# MIXR_Processing_-_SD_Card.net
KiCad netlist of a schematic drawn in Altium Designer
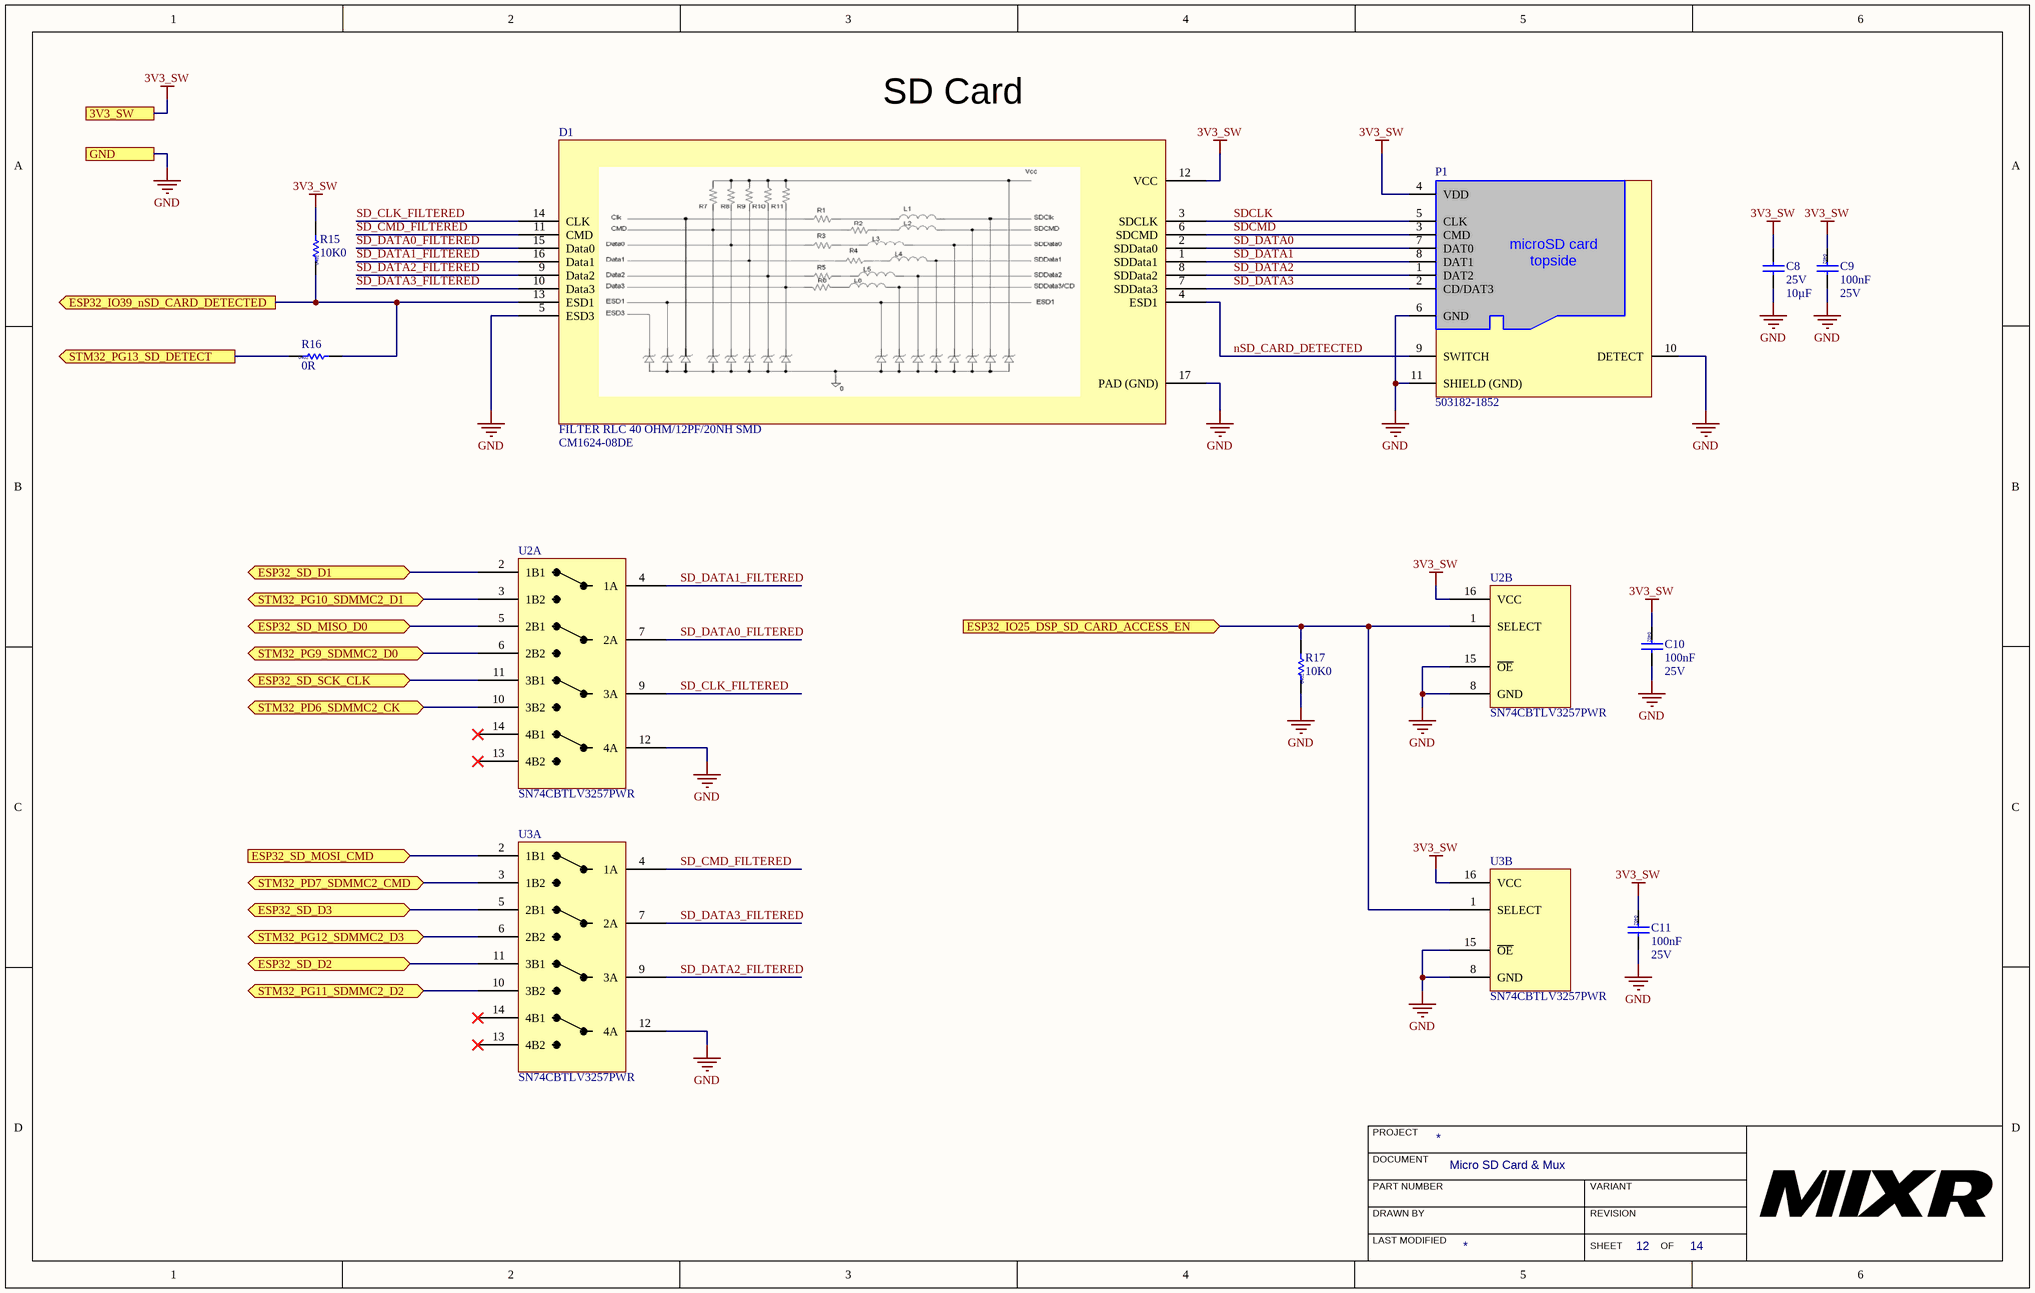
[diagram p0: MIXR Processing - SD Card.SchDoc]

(export (version "E")
  (design (tool "Eeschema 10.0.6"))
  (components
    (comp (ref "C8")
      (value "CAP CER 10uF 25V 10% X5R 0805")
      (footprint "CAP, 0805")
      (description "10µF ±10% 25V Ceramic Capacitor X5R 0805 (2012 Metric)")
      (fields
        (field (name "MANUFACTURER") "Murata Electronics North America")
        (field (name "MANUFACTURER PART NUMBER") "GRM21BR61E106KA73L")
        (field (name "VOLTAGE - RATED") "25V")
        (field (name "CAPACITANCE") "10µF")
      )
      (libsource (lib "Schematic Diagrams") (part "CAP CER 10uF 25V 10% X5R 0805"))
    )
    (comp (ref "C9")
      (value "CAP CER 0.1UF 16V X7R 0402")
      (footprint "CAP 0402")
      (description "Cap Ceramic 0.1uF 25V X7R 10% SMD 0402 125C Paper T/R")
      (fields
        (field (name "TOLERANCE") "10%")
        (field (name "CAPACITANCE") "100nF")
        (field (name "VOLTAGE") "25V")
        (field (name "MANUFACTURER") "Murata")
      )
      (libsource (lib "Schematic Diagrams") (part "CAP CER 0.1UF 16V X7R 0402"))
    )
    (comp (ref "C10")
      (value "CAP CER 0.1UF 16V X7R 0402")
      (footprint "CAP 0402")
      (description "Cap Ceramic 0.1uF 25V X7R 10% SMD 0402 125C Paper T/R")
      (fields
        (field (name "TOLERANCE") "10%")
        (field (name "CAPACITANCE") "100nF")
        (field (name "VOLTAGE") "25V")
        (field (name "MANUFACTURER") "Murata")
      )
      (libsource (lib "Schematic Diagrams") (part "CAP CER 0.1UF 16V X7R 0402"))
    )
    (comp (ref "C11")
      (value "CAP CER 0.1UF 16V X7R 0402")
      (footprint "CAP 0402")
      (description "Cap Ceramic 0.1uF 25V X7R 10% SMD 0402 125C Paper T/R")
      (fields
        (field (name "TOLERANCE") "10%")
        (field (name "CAPACITANCE") "100nF")
        (field (name "VOLTAGE") "25V")
        (field (name "MANUFACTURER") "Murata")
      )
      (libsource (lib "Schematic Diagrams") (part "CAP CER 0.1UF 16V X7R 0402"))
    )
    (comp (ref "D1")
      (value "FILTER RLC 40 OHM/12PF/20NH SMD")
      (footprint "QFN0P135X330X55_HS-17M")
      (description "RLC EMI Filter 3rd Order Low Pass 6 Channel R = 40Ohms, C = 12pF, L = 20nH 16-UFDFN Exposed Pad")
      (fields (field (name "MANUFACTURER PART NUMBER 1") "CM1624-08DE"))
      (libsource (lib "Schematic Diagrams") (part "FILTER RLC 40 OHM/12PF/20NH SMD"))
    )
    (comp (ref "P1")
      (value "CONN MICRO-SD ULTRA-LOW 8CKT")
      (footprint "CONN MICRO-SD HOLDER MOLEX 503182-1852")
      (description "9 (8 + 1) Position Card Connector microSD™ Surface Mount, Right Angle Gold")
      (fields (field (name "MANUFACTURER") "Molex") (field (name "MANUFACTURER PART NUMBER") "503182-1852"))
      (libsource (lib "Schematic Diagrams") (part "CONN MICRO-SD ULTRA-LOW 8CKT"))
    )
    (comp (ref "R15")
      (value "RES 10K OHM 1% 1/16W 0402")
      (footprint "RES 0402")
      (description "Surface Mount Thick Film Resistor, Rc Series, 10 Kohm, 62.5 Mw, - 1%, 50 V, 0402 [1005 Metric]")
      (fields
        (field (name "TOLERANCE") "1%")
        (field (name "RESISTANCE") "10K0")
        (field (name "MANUFACTURER") "Yageo")
      )
      (libsource (lib "Schematic Diagrams") (part "RES 10K OHM 1% 1/16W 0402"))
    )
    (comp (ref "R16")
      (value "RES 0.0 OHM 1% 1/16W 0402")
      (footprint "RES 0402")
      (description "RES SMD 0 OHM JUMPER 1/16W 0402")
      (fields
        (field (name "RESISTANCE") "0R")
        (field (name "MANUFACTURER") "Yageo")
        (field (name "MANUFACTURER PART NUMBER") "RC0402JR-070RL")
      )
      (libsource (lib "Schematic Diagrams") (part "RES 0.0 OHM 1% 1/16W 0402"))
    )
    (comp (ref "R17")
      (value "RES 10K OHM 1% 1/16W 0402")
      (footprint "RES 0402")
      (description "Surface Mount Thick Film Resistor, Rc Series, 10 Kohm, 62.5 Mw, - 1%, 50 V, 0402 [1005 Metric]")
      (fields
        (field (name "TOLERANCE") "1%")
        (field (name "RESISTANCE") "10K0")
        (field (name "MANUFACTURER") "Yageo")
      )
      (libsource (lib "Schematic Diagrams") (part "RES 10K OHM 1% 1/16W 0402"))
    )
    (comp (ref "U2")
      (value "IC MUX/DEMUX 4-BIT 1-OF-2 16-TSSOP")
      (footprint "TSOP65P640X120-16N")
      (description "TEXAS INSTRUMENTS         SN74CBTLV3257PWR            1 TO 2 QUAD FET MUX/DEMUX, TSSOP-16")
      (fields
        (field (name "MANUFACTURER") "Texas Instruments")
        (field (name "MANUFACTURER PART NUMBER") "SN74CBTLV3257PWR")
      )
      (libsource (lib "Schematic Diagrams") (part "IC MUX/DEMUX 4-BIT 1-OF-2 16-TSSOP"))
    )
    (comp (ref "U3")
      (value "IC MUX/DEMUX 4-BIT 1-OF-2 16-TSSOP")
      (footprint "TSOP65P640X120-16N")
      (description "TEXAS INSTRUMENTS         SN74CBTLV3257PWR            1 TO 2 QUAD FET MUX/DEMUX, TSSOP-16")
      (fields
        (field (name "MANUFACTURER") "Texas Instruments")
        (field (name "MANUFACTURER PART NUMBER") "SN74CBTLV3257PWR")
      )
      (libsource (lib "") (part "IC MUX/DEMUX 4-BIT 1-OF-2 16-TSSOP_1"))
    )
  )
  (nets
    (net (code "1") (name "/ESP32_IO25_DSP_SD_CARD_ACCESS_EN") (class "Default")
      (node (ref "R17") (pin "2") (pinfunction "2_2") (pintype "passive"))
      (node (ref "U2") (pin "1") (pinfunction "SELECT_1") (pintype "passive"))
      (node (ref "U3") (pin "1") (pinfunction "SELECT_1") (pintype "passive"))
    )
    (net (code "2") (name "/ESP32_IO39_nSD_CARD_DETECTED") (class "Default")
      (node (ref "D1") (pin "13") (pinfunction "ESD1_13") (pintype "passive"))
      (node (ref "R15") (pin "1") (pinfunction "1_1") (pintype "passive"))
      (node (ref "R16") (pin "2") (pinfunction "2_2") (pintype "passive"))
    )
    (net (code "3") (name "/ESP32_SD_D1") (class "Default")
      (node (ref "U2") (pin "2") (pinfunction "1B1_2") (pintype "passive"))
    )
    (net (code "4") (name "/ESP32_SD_D2") (class "Default")
      (node (ref "U3") (pin "11") (pinfunction "3B1_11") (pintype "passive"))
    )
    (net (code "5") (name "/ESP32_SD_D3") (class "Default")
      (node (ref "U3") (pin "5") (pinfunction "2B1_5") (pintype "passive"))
    )
    (net (code "6") (name "/ESP32_SD_MISO_D0") (class "Default")
      (node (ref "U2") (pin "5") (pinfunction "2B1_5") (pintype "passive"))
    )
    (net (code "7") (name "/ESP32_SD_MOSI_CMD") (class "Default")
      (node (ref "U3") (pin "2") (pinfunction "1B1_2") (pintype "passive"))
    )
    (net (code "8") (name "/ESP32_SD_SCK_CLK") (class "Default")
      (node (ref "U2") (pin "11") (pinfunction "3B1_11") (pintype "passive"))
    )
    (net (code "9") (name "/SDCLK") (class "Default")
      (node (ref "D1") (pin "3") (pinfunction "SDCLK_3") (pintype "passive"))
      (node (ref "P1") (pin "5") (pinfunction "CLK_5") (pintype "passive"))
    )
    (net (code "10") (name "/SDCMD") (class "Default")
      (node (ref "D1") (pin "6") (pinfunction "SDCMD_6") (pintype "passive"))
      (node (ref "P1") (pin "3") (pinfunction "CMD_3") (pintype "passive"))
    )
    (net (code "11") (name "/SD_CLK_FILTERED") (class "Default")
      (node (ref "D1") (pin "14") (pinfunction "CLK_14") (pintype "passive"))
      (node (ref "U2") (pin "9") (pinfunction "3A_9") (pintype "passive"))
    )
    (net (code "12") (name "/SD_CMD_FILTERED") (class "Default")
      (node (ref "D1") (pin "11") (pinfunction "CMD_11") (pintype "passive"))
      (node (ref "U3") (pin "4") (pinfunction "1A_4") (pintype "passive"))
    )
    (net (code "13") (name "/SD_DATA0") (class "Default")
      (node (ref "D1") (pin "2") (pinfunction "SDData0_2") (pintype "passive"))
      (node (ref "P1") (pin "7") (pinfunction "DAT0_7") (pintype "passive"))
    )
    (net (code "14") (name "/SD_DATA0_FILTERED") (class "Default")
      (node (ref "D1") (pin "15") (pinfunction "Data0_15") (pintype "passive"))
      (node (ref "U2") (pin "7") (pinfunction "2A_7") (pintype "passive"))
    )
    (net (code "15") (name "/SD_DATA1") (class "Default")
      (node (ref "D1") (pin "1") (pinfunction "SDData1_1") (pintype "passive"))
      (node (ref "P1") (pin "8") (pinfunction "DAT1_8") (pintype "passive"))
    )
    (net (code "16") (name "/SD_DATA1_FILTERED") (class "Default")
      (node (ref "D1") (pin "16") (pinfunction "Data1_16") (pintype "passive"))
      (node (ref "U2") (pin "4") (pinfunction "1A_4") (pintype "passive"))
    )
    (net (code "17") (name "/SD_DATA2") (class "Default")
      (node (ref "D1") (pin "8") (pinfunction "SDData2_8") (pintype "passive"))
      (node (ref "P1") (pin "1") (pinfunction "DAT2_1") (pintype "passive"))
    )
    (net (code "18") (name "/SD_DATA2_FILTERED") (class "Default")
      (node (ref "D1") (pin "9") (pinfunction "Data2_9") (pintype "passive"))
      (node (ref "U3") (pin "9") (pinfunction "3A_9") (pintype "passive"))
    )
    (net (code "19") (name "/SD_DATA3") (class "Default")
      (node (ref "D1") (pin "7") (pinfunction "SDData3_7") (pintype "passive"))
      (node (ref "P1") (pin "2") (pinfunction "CD/DAT3_2") (pintype "passive"))
    )
    (net (code "20") (name "/SD_DATA3_FILTERED") (class "Default")
      (node (ref "D1") (pin "10") (pinfunction "Data3_10") (pintype "passive"))
      (node (ref "U3") (pin "7") (pinfunction "2A_7") (pintype "passive"))
    )
    (net (code "21") (name "/STM32_PD6_SDMMC2_CK") (class "Default")
      (node (ref "U2") (pin "10") (pinfunction "3B2_10") (pintype "passive"))
    )
    (net (code "22") (name "/STM32_PD7_SDMMC2_CMD") (class "Default")
      (node (ref "U3") (pin "3") (pinfunction "1B2_3") (pintype "passive"))
    )
    (net (code "23") (name "/STM32_PG9_SDMMC2_D0") (class "Default")
      (node (ref "U2") (pin "6") (pinfunction "2B2_6") (pintype "passive"))
    )
    (net (code "24") (name "/STM32_PG10_SDMMC2_D1") (class "Default")
      (node (ref "U2") (pin "3") (pinfunction "1B2_3") (pintype "passive"))
    )
    (net (code "25") (name "/STM32_PG11_SDMMC2_D2") (class "Default")
      (node (ref "U3") (pin "10") (pinfunction "3B2_10") (pintype "passive"))
    )
    (net (code "26") (name "/STM32_PG12_SDMMC2_D3") (class "Default")
      (node (ref "U3") (pin "6") (pinfunction "2B2_6") (pintype "passive"))
    )
    (net (code "27") (name "/STM32_PG13_SD_DETECT") (class "Default")
      (node (ref "R16") (pin "1") (pinfunction "1_1") (pintype "passive"))
    )
    (net (code "28") (name "/nSD_CARD_DETECTED") (class "Default")
      (node (ref "D1") (pin "4") (pinfunction "ESD1_4") (pintype "passive"))
      (node (ref "P1") (pin "9") (pinfunction "SWITCH_9") (pintype "passive"))
    )
    (net (code "29") (name "3V3_SW") (class "Default")
      (node (ref "C10") (pin "1") (pinfunction "1_1") (pintype "passive"))
      (node (ref "C11") (pin "1") (pinfunction "1_1") (pintype "passive"))
      (node (ref "C8") (pin "1") (pinfunction "1_1") (pintype "passive"))
      (node (ref "C9") (pin "1") (pinfunction "1_1") (pintype "passive"))
      (node (ref "D1") (pin "12") (pinfunction "VCC_12") (pintype "passive"))
      (node (ref "P1") (pin "4") (pinfunction "VDD_4") (pintype "passive"))
      (node (ref "R15") (pin "2") (pinfunction "2_2") (pintype "passive"))
      (node (ref "U2") (pin "16") (pinfunction "VCC_16") (pintype "passive"))
      (node (ref "U3") (pin "16") (pinfunction "VCC_16") (pintype "passive"))
    )
    (net (code "30") (name "GND") (class "Default")
      (node (ref "C10") (pin "2") (pinfunction "2_2") (pintype "passive"))
      (node (ref "C11") (pin "2") (pinfunction "2_2") (pintype "passive"))
      (node (ref "C8") (pin "2") (pinfunction "2_2") (pintype "passive"))
      (node (ref "C9") (pin "2") (pinfunction "2_2") (pintype "passive"))
      (node (ref "D1") (pin "17") (pinfunction "PAD_(GND)_17") (pintype "passive"))
      (node (ref "D1") (pin "5") (pinfunction "ESD3_5") (pintype "passive"))
      (node (ref "P1") (pin "10") (pinfunction "DETECT_10") (pintype "passive"))
      (node (ref "P1") (pin "11") (pinfunction "SHIELD_(GND)_11") (pintype "passive"))
      (node (ref "P1") (pin "6") (pinfunction "GND_6") (pintype "passive"))
      (node (ref "R17") (pin "1") (pinfunction "1_1") (pintype "passive"))
      (node (ref "U2") (pin "12") (pinfunction "4A_12") (pintype "passive"))
      (node (ref "U2") (pin "15") (pinfunction "~{OE}_15") (pintype "passive"))
      (node (ref "U2") (pin "8") (pinfunction "GND_8") (pintype "passive"))
      (node (ref "U3") (pin "12") (pinfunction "4A_12") (pintype "passive"))
      (node (ref "U3") (pin "15") (pinfunction "~{OE}_15") (pintype "passive"))
      (node (ref "U3") (pin "8") (pinfunction "GND_8") (pintype "passive"))
    )
    (net (code "31") (name "unconnected-(U2A-4B1-Pad14)") (class "Default")
      (node (ref "U2") (pin "14") (pinfunction "4B1_14") (pintype "passive+no_connect"))
    )
    (net (code "32") (name "unconnected-(U2A-4B2-Pad13)") (class "Default")
      (node (ref "U2") (pin "13") (pinfunction "4B2_13") (pintype "passive+no_connect"))
    )
    (net (code "33") (name "unconnected-(U3A-4B1-Pad14)") (class "Default")
      (node (ref "U3") (pin "14") (pinfunction "4B1_14") (pintype "passive+no_connect"))
    )
    (net (code "34") (name "unconnected-(U3A-4B2-Pad13)") (class "Default")
      (node (ref "U3") (pin "13") (pinfunction "4B2_13") (pintype "passive+no_connect"))
    )
  )
)
